# RF_Transceiver_LM6002D_Power.net
KiCad netlist of a schematic drawn in Altium Designer
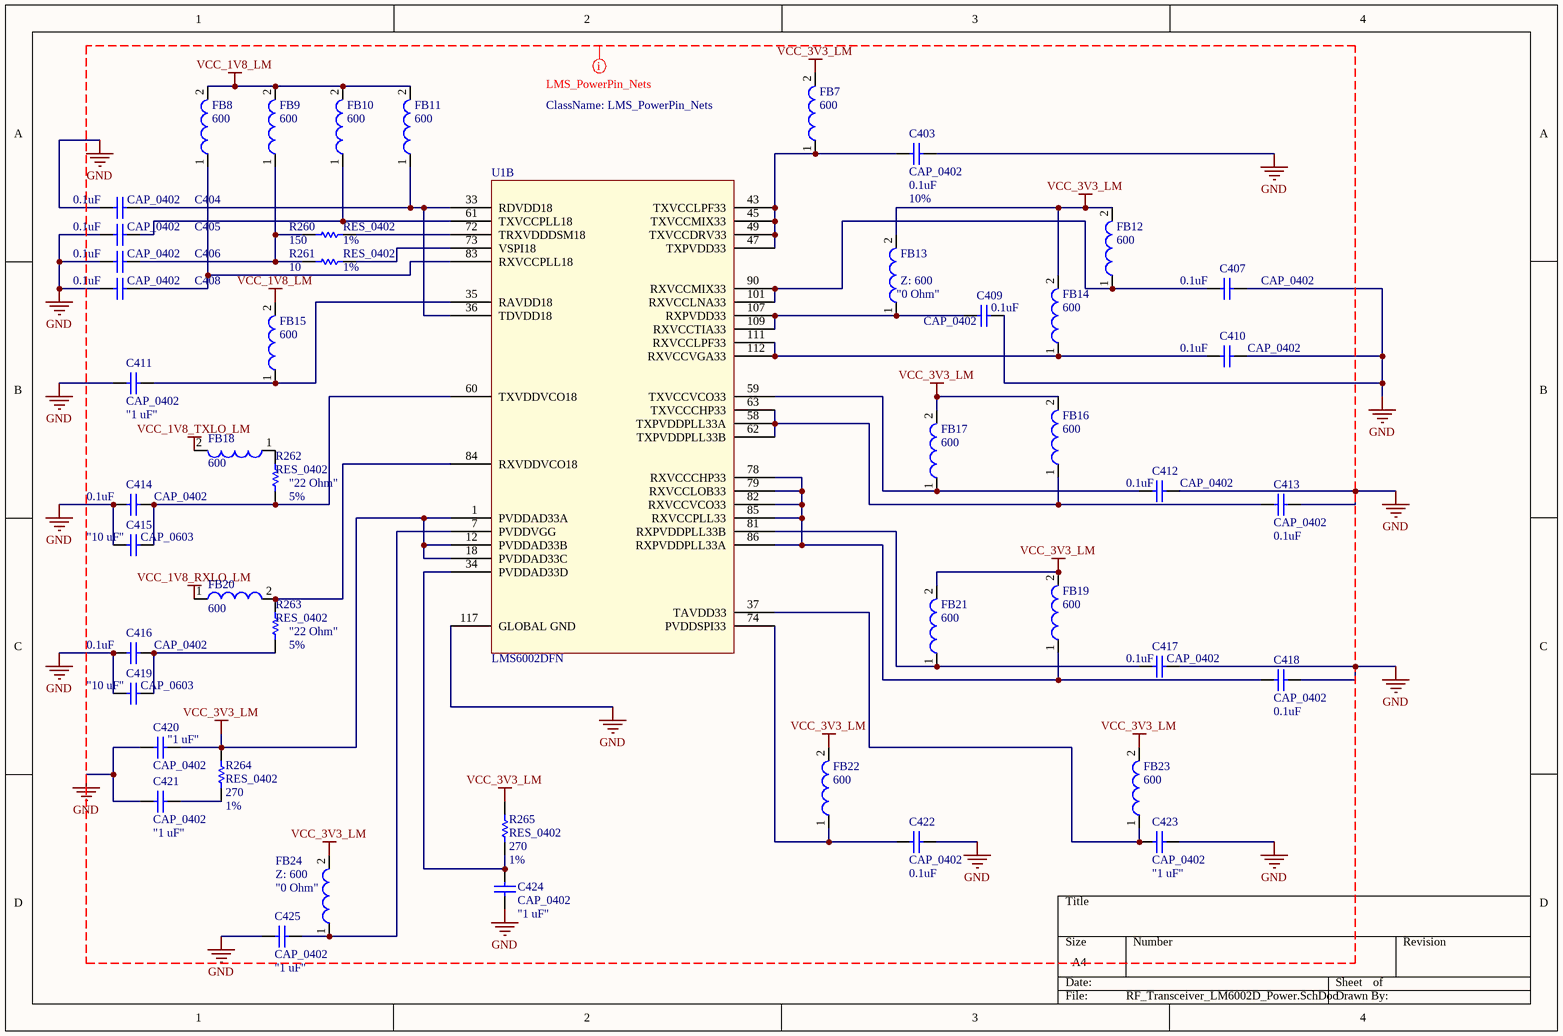
[diagram p0: RF_Transceiver_LM6002D_Power.SchDoc]

(export (version "E")
  (design (tool "Eeschema 10.0.6"))
  (components
    (comp (ref "C403")
      (value "CAP_0402")
      (footprint "CAPC0402(1005)60_N")
      (description "0.1uf, ceramic, 10%, 6.3V, X5R, 0402")
      (fields
        (field (name "ALTIUM_VALUE") "0.1uF")
        (field (name "TOLERANCE") "10%")
        (field (name "PART NUMBER") "C1005X5R0J104K")
        (field (name "MANUFACTURER") "TDK Corporation")
      )
      (libsource (lib "COMRAD_Database") (part "CAP_0402"))
    )
    (comp (ref "C404")
      (value "CAP_0402")
      (footprint "CAPC0402(1005)60_N")
      (description "0.1uf, ceramic, 10%, 6.3V, X5R, 0402")
      (fields
        (field (name "ALTIUM_VALUE") "0.1uF")
        (field (name "TOLERANCE") "10%")
        (field (name "PART NUMBER") "C1005X5R0J104K")
      )
      (libsource (lib "COMRAD_Database") (part "CAP_0402"))
    )
    (comp (ref "C405")
      (value "CAP_0402")
      (footprint "CAPC0402(1005)60_N")
      (description "0.1uf, ceramic, 10%, 6.3V, X5R, 0402")
      (fields
        (field (name "ALTIUM_VALUE") "0.1uF")
        (field (name "TOLERANCE") "10%")
        (field (name "PART NUMBER") "C1005X5R0J104K")
      )
      (libsource (lib "COMRAD_Database") (part "CAP_0402"))
    )
    (comp (ref "C406")
      (value "CAP_0402")
      (footprint "CAPC0402(1005)60_N")
      (description "0.1uf, ceramic, 10%, 6.3V, X5R, 0402")
      (fields
        (field (name "ALTIUM_VALUE") "0.1uF")
        (field (name "TOLERANCE") "10%")
        (field (name "PART NUMBER") "C1005X5R0J104K")
      )
      (libsource (lib "COMRAD_Database") (part "CAP_0402"))
    )
    (comp (ref "C407")
      (value "CAP_0402")
      (footprint "CAPC0402(1005)60_N")
      (description "0.1uf, ceramic, 10%, 6.3V, X5R, 0402")
      (fields
        (field (name "ALTIUM_VALUE") "0.1uF")
        (field (name "TOLERANCE") "10%")
        (field (name "PART NUMBER") "C1005X5R0J104K")
      )
      (libsource (lib "COMRAD_Database") (part "CAP_0402"))
    )
    (comp (ref "C408")
      (value "CAP_0402")
      (footprint "CAPC0402(1005)60_N")
      (description "0.1uf, ceramic, 10%, 6.3V, X5R, 0402")
      (fields
        (field (name "ALTIUM_VALUE") "0.1uF")
        (field (name "TOLERANCE") "10%")
        (field (name "PART NUMBER") "C1005X5R0J104K")
      )
      (libsource (lib "COMRAD_Database") (part "CAP_0402"))
    )
    (comp (ref "C409")
      (value "CAP_0402")
      (footprint "CAPC0402(1005)60_N")
      (description "0.1uf, ceramic, 10%, 6.3V, X5R, 0402")
      (fields
        (field (name "ALTIUM_VALUE") "0.1uF")
        (field (name "TOLERANCE") "10%")
        (field (name "PART NUMBER") "C1005X5R0J104K")
      )
      (libsource (lib "COMRAD_Database") (part "CAP_0402"))
    )
    (comp (ref "C410")
      (value "CAP_0402")
      (footprint "CAPC0402(1005)60_N")
      (description "0.1uf, ceramic, 10%, 6.3V, X5R, 0402")
      (fields
        (field (name "ALTIUM_VALUE") "0.1uF")
        (field (name "TOLERANCE") "10%")
        (field (name "PART NUMBER") "C1005X5R0J104K")
      )
      (libsource (lib "COMRAD_Database") (part "CAP_0402"))
    )
    (comp (ref "C411")
      (value "CAP_0402")
      (footprint "CAPC0402(1005)60_N")
      (description "C 1 uF 10V 0402 X5R")
      (fields
        (field (name "ALTIUM_VALUE") "\"1 uF\"")
        (field (name "PART NUMBER") "\"MCCA000506\"")
        (field (name "MANUFACTURER") "MULTICOMP")
      )
      (libsource (lib "COMRAD_Database") (part "CAP_0402"))
    )
    (comp (ref "C412")
      (value "CAP_0402")
      (footprint "CAPC0402(1005)60_N")
      (description "0.1uf, ceramic, 10%, 6.3V, X5R, 0402")
      (fields
        (field (name "ALTIUM_VALUE") "0.1uF")
        (field (name "TOLERANCE") "10%")
        (field (name "PART NUMBER") "C1005X5R0J104K")
      )
      (libsource (lib "COMRAD_Database") (part "CAP_0402"))
    )
    (comp (ref "C413")
      (value "CAP_0402")
      (footprint "CAPC0402(1005)60_N")
      (description "0.1uf, ceramic, 10%, 6.3V, X5R, 0402")
      (fields
        (field (name "ALTIUM_VALUE") "0.1uF")
        (field (name "TOLERANCE") "10%")
        (field (name "PART NUMBER") "C1005X5R0J104K")
      )
      (libsource (lib "COMRAD_Database") (part "CAP_0402"))
    )
    (comp (ref "C414")
      (value "CAP_0402")
      (footprint "CAPC0402(1005)60_N")
      (description "0.1uf, ceramic, 10%, 6.3V, X5R, 0402")
      (fields
        (field (name "ALTIUM_VALUE") "0.1uF")
        (field (name "TOLERANCE") "10%")
        (field (name "PART NUMBER") "C1005X5R0J104K")
      )
      (libsource (lib "COMRAD_Database") (part "CAP_0402"))
    )
    (comp (ref "C415")
      (value "CAP_0603")
      (footprint "CAPC0603(1608)100_N:CAPC0603(1608)100_N")
      (description "C 10 uF 6.3 V 0603 X5R")
      (fields
        (field (name "ALTIUM_VALUE") "\"10 uF\"")
        (field (name "PART NUMBER") "\"MCCA000517\"")
        (field (name "MANUFACTURER") "Multicomp")
      )
      (libsource (lib "COMRAD_Database") (part "CAP_0603"))
    )
    (comp (ref "C416")
      (value "CAP_0402")
      (footprint "CAPC0402(1005)60_N")
      (description "0.1uf, ceramic, 10%, 6.3V, X5R, 0402")
      (fields
        (field (name "ALTIUM_VALUE") "0.1uF")
        (field (name "TOLERANCE") "10%")
        (field (name "PART NUMBER") "C1005X5R0J104K")
      )
      (libsource (lib "COMRAD_Database") (part "CAP_0402"))
    )
    (comp (ref "C417")
      (value "CAP_0402")
      (footprint "CAPC0402(1005)60_N")
      (description "0.1uf, ceramic, 10%, 6.3V, X5R, 0402")
      (fields
        (field (name "ALTIUM_VALUE") "0.1uF")
        (field (name "TOLERANCE") "10%")
        (field (name "PART NUMBER") "C1005X5R0J104K")
      )
      (libsource (lib "COMRAD_Database") (part "CAP_0402"))
    )
    (comp (ref "C418")
      (value "CAP_0402")
      (footprint "CAPC0402(1005)60_N")
      (description "0.1uf, ceramic, 10%, 6.3V, X5R, 0402")
      (fields
        (field (name "ALTIUM_VALUE") "0.1uF")
        (field (name "TOLERANCE") "10%")
        (field (name "PART NUMBER") "C1005X5R0J104K")
      )
      (libsource (lib "COMRAD_Database") (part "CAP_0402"))
    )
    (comp (ref "C419")
      (value "CAP_0603")
      (footprint "CAPC0603(1608)100_N:CAPC0603(1608)100_N")
      (description "C 10 uF 6.3 V 0603 X5R")
      (fields
        (field (name "ALTIUM_VALUE") "\"10 uF\"")
        (field (name "PART NUMBER") "\"MCCA000517\"")
        (field (name "MANUFACTURER") "Multicomp")
      )
      (libsource (lib "COMRAD_Database") (part "CAP_0603"))
    )
    (comp (ref "C420")
      (value "CAP_0402")
      (footprint "CAPC0402(1005)60_N")
      (description "C 1 uF 10V 0402 X5R")
      (fields
        (field (name "ALTIUM_VALUE") "\"1 uF\"")
        (field (name "PART NUMBER") "\"MCCA000506\"")
        (field (name "MANUFACTURER") "MULTICOMP")
      )
      (libsource (lib "COMRAD_Database") (part "CAP_0402"))
    )
    (comp (ref "C421")
      (value "CAP_0402")
      (footprint "CAPC0402(1005)60_N")
      (description "C 1 uF 10V 0402 X5R")
      (fields
        (field (name "ALTIUM_VALUE") "\"1 uF\"")
        (field (name "PART NUMBER") "\"MCCA000506\"")
        (field (name "MANUFACTURER") "MULTICOMP")
      )
      (libsource (lib "COMRAD_Database") (part "CAP_0402"))
    )
    (comp (ref "C422")
      (value "CAP_0402")
      (footprint "CAPC0402(1005)60_N")
      (description "0.1uf, ceramic, 10%, 6.3V, X5R, 0402")
      (fields
        (field (name "ALTIUM_VALUE") "0.1uF")
        (field (name "TOLERANCE") "10%")
        (field (name "PART NUMBER") "C1005X5R0J104K")
      )
      (libsource (lib "COMRAD_Database") (part "CAP_0402"))
    )
    (comp (ref "C423")
      (value "CAP_0402")
      (footprint "CAPC0402(1005)60_N")
      (description "C 1 uF 10V 0402 X5R")
      (fields
        (field (name "ALTIUM_VALUE") "\"1 uF\"")
        (field (name "PART NUMBER") "\"MCCA000506\"")
        (field (name "MANUFACTURER") "MULTICOMP")
      )
      (libsource (lib "COMRAD_Database") (part "CAP_0402"))
    )
    (comp (ref "C424")
      (value "CAP_0402")
      (footprint "CAPC0402(1005)60_N")
      (description "C 1 uF 10V 0402 X5R")
      (fields
        (field (name "ALTIUM_VALUE") "\"1 uF\"")
        (field (name "PART NUMBER") "\"MCCA000506\"")
        (field (name "MANUFACTURER") "MULTICOMP")
      )
      (libsource (lib "COMRAD_Database") (part "CAP_0402"))
    )
    (comp (ref "C425")
      (value "CAP_0402")
      (footprint "CAPC0402(1005)60_N")
      (description "C 1 uF 10V 0402 X5R")
      (fields
        (field (name "ALTIUM_VALUE") "\"1 uF\"")
        (field (name "PART NUMBER") "\"MCCA000506\"")
        (field (name "MANUFACTURER") "MULTICOMP")
      )
      (libsource (lib "COMRAD_Database") (part "CAP_0402"))
    )
    (comp (ref "FB7")
      (value "FerriteBead")
      (footprint "Inductor0402(1005)")
      (description "Ferrite 300mA 600ohm 0402")
      (fields
        (field (name "Z") "600")
        (field (name "PART NUMBER") "\"MMZ1005S601C\"")
        (field (name "MANUFACTURER") "TDK")
      )
      (libsource (lib "COMRAD_Database") (part "FerriteBead"))
    )
    (comp (ref "FB8")
      (value "FerriteBead")
      (footprint "Inductor0402(1005)")
      (description "Ferrite 300mA 600ohm 0402")
      (fields
        (field (name "Z") "600")
        (field (name "PART NUMBER") "\"MMZ1005S601C\"")
        (field (name "MANUFACTURER") "TDK")
      )
      (libsource (lib "COMRAD_Database") (part "FerriteBead"))
    )
    (comp (ref "FB9")
      (value "FerriteBead")
      (footprint "Inductor0402(1005)")
      (description "Ferrite 300mA 600ohm 0402")
      (fields
        (field (name "Z") "600")
        (field (name "PART NUMBER") "\"MMZ1005S601C\"")
        (field (name "MANUFACTURER") "TDK")
      )
      (libsource (lib "COMRAD_Database") (part "FerriteBead"))
    )
    (comp (ref "FB10")
      (value "FerriteBead")
      (footprint "Inductor0402(1005)")
      (description "Ferrite 300mA 600ohm 0402")
      (fields
        (field (name "Z") "600")
        (field (name "PART NUMBER") "\"MMZ1005S601C\"")
        (field (name "MANUFACTURER") "TDK")
      )
      (libsource (lib "COMRAD_Database") (part "FerriteBead"))
    )
    (comp (ref "FB11")
      (value "FerriteBead")
      (footprint "Inductor0402(1005)")
      (description "Ferrite 300mA 600ohm 0402")
      (fields
        (field (name "Z") "600")
        (field (name "PART NUMBER") "\"MMZ1005S601C\"")
        (field (name "MANUFACTURER") "TDK")
      )
      (libsource (lib "COMRAD_Database") (part "FerriteBead"))
    )
    (comp (ref "FB12")
      (value "FerriteBead")
      (footprint "Inductor0402(1005)")
      (description "Ferrite 300mA 600ohm 0402")
      (fields
        (field (name "Z") "600")
        (field (name "PART NUMBER") "\"MMZ1005S601C\"")
        (field (name "MANUFACTURER") "TDK")
      )
      (libsource (lib "COMRAD_Database") (part "FerriteBead"))
    )
    (comp (ref "FB13")
      (value "\"0 Ohm\"")
      (footprint "Inductor0402(1005)")
      (description "Ferrite 300mA 600ohm 0402")
      (fields
        (field (name "Z") "600")
        (field (name "PART NUMBER") "\"MMZ1005S601C\"")
        (field (name "MANUFACTURER") "TDK")
      )
      (libsource (lib "COMRAD_Database") (part "FerriteBead"))
    )
    (comp (ref "FB14")
      (value "FerriteBead")
      (footprint "Inductor0402(1005)")
      (description "Ferrite 300mA 600ohm 0402")
      (fields
        (field (name "Z") "600")
        (field (name "PART NUMBER") "\"MMZ1005S601C\"")
        (field (name "MANUFACTURER") "TDK")
      )
      (libsource (lib "COMRAD_Database") (part "FerriteBead"))
    )
    (comp (ref "FB15")
      (value "FerriteBead")
      (footprint "Inductor0402(1005)")
      (description "Ferrite 300mA 600ohm 0402")
      (fields
        (field (name "Z") "600")
        (field (name "PART NUMBER") "\"MMZ1005S601C\"")
        (field (name "MANUFACTURER") "TDK")
      )
      (libsource (lib "COMRAD_Database") (part "FerriteBead"))
    )
    (comp (ref "FB16")
      (value "FerriteBead")
      (footprint "Inductor0402(1005)")
      (description "Ferrite 300mA 600ohm 0402")
      (fields
        (field (name "Z") "600")
        (field (name "PART NUMBER") "\"MMZ1005S601C\"")
        (field (name "MANUFACTURER") "TDK")
      )
      (libsource (lib "COMRAD_Database") (part "FerriteBead"))
    )
    (comp (ref "FB17")
      (value "FerriteBead")
      (footprint "Inductor0402(1005)")
      (description "Ferrite 300mA 600ohm 0402")
      (fields
        (field (name "Z") "600")
        (field (name "PART NUMBER") "\"MMZ1005S601C\"")
        (field (name "MANUFACTURER") "TDK")
      )
      (libsource (lib "COMRAD_Database") (part "FerriteBead"))
    )
    (comp (ref "FB18")
      (value "FerriteBead")
      (footprint "Inductor0402(1005)")
      (description "Ferrite 300mA 600ohm 0402")
      (fields
        (field (name "Z") "600")
        (field (name "PART NUMBER") "\"MMZ1005S601C\"")
        (field (name "MANUFACTURER") "TDK")
      )
      (libsource (lib "COMRAD_Database") (part "FerriteBead"))
    )
    (comp (ref "FB19")
      (value "FerriteBead")
      (footprint "Inductor0402(1005)")
      (description "Ferrite 300mA 600ohm 0402")
      (fields
        (field (name "Z") "600")
        (field (name "PART NUMBER") "\"MMZ1005S601C\"")
        (field (name "MANUFACTURER") "TDK")
      )
      (libsource (lib "COMRAD_Database") (part "FerriteBead"))
    )
    (comp (ref "FB20")
      (value "FerriteBead")
      (footprint "Inductor0402(1005)")
      (description "Ferrite 300mA 600ohm 0402")
      (fields
        (field (name "Z") "600")
        (field (name "PART NUMBER") "\"MMZ1005S601C\"")
        (field (name "MANUFACTURER") "TDK")
      )
      (libsource (lib "COMRAD_Database") (part "FerriteBead"))
    )
    (comp (ref "FB21")
      (value "FerriteBead")
      (footprint "Inductor0402(1005)")
      (description "Ferrite 300mA 600ohm 0402")
      (fields
        (field (name "Z") "600")
        (field (name "PART NUMBER") "\"MMZ1005S601C\"")
        (field (name "MANUFACTURER") "TDK")
      )
      (libsource (lib "COMRAD_Database") (part "FerriteBead"))
    )
    (comp (ref "FB22")
      (value "FerriteBead")
      (footprint "Inductor0402(1005)")
      (description "Ferrite 300mA 600ohm 0402")
      (fields
        (field (name "Z") "600")
        (field (name "PART NUMBER") "\"MMZ1005S601C\"")
        (field (name "MANUFACTURER") "TDK")
      )
      (libsource (lib "COMRAD_Database") (part "FerriteBead"))
    )
    (comp (ref "FB23")
      (value "FerriteBead")
      (footprint "Inductor0402(1005)")
      (description "Ferrite 300mA 600ohm 0402")
      (fields
        (field (name "Z") "600")
        (field (name "PART NUMBER") "\"MMZ1005S601C\"")
        (field (name "MANUFACTURER") "TDK")
      )
      (libsource (lib "COMRAD_Database") (part "FerriteBead"))
    )
    (comp (ref "FB24")
      (value "\"0 Ohm\"")
      (footprint "Inductor0402(1005)")
      (description "Ferrite 300mA 600ohm 0402")
      (fields
        (field (name "Z") "600")
        (field (name "PART NUMBER") "\"MMZ1005S601C\"")
        (field (name "MANUFACTURER") "TDK")
      )
      (libsource (lib "COMRAD_Database") (part "FerriteBead"))
    )
    (comp (ref "R260")
      (value "RES_0402")
      (footprint "RESC0402(1005)_N")
      (description "RES 150 OHM 1/10W 1% 0402 SMD")
      (fields
        (field (name "ALTIUM_VALUE") "150")
        (field (name "TOLERANCE") "1%")
        (field (name "PART NUMBER") "ERJ-2RKF1500X")
        (field (name "MANUFACTURER") "Panasonic Electronic Components")
      )
      (libsource (lib "COMRAD_Database") (part "RES_0402"))
    )
    (comp (ref "R261")
      (value "RES_0402")
      (footprint "RESC0402(1005)_N")
      (description "RES 10.0 OHM 1/10W 1% 0402 SMD")
      (fields
        (field (name "ALTIUM_VALUE") "10")
        (field (name "TOLERANCE") "1%")
        (field (name "PART NUMBER") "ERJ-2RKF10R0X")
        (field (name "MANUFACTURER") "Panasonic Electronic Components")
      )
      (libsource (lib "COMRAD_Database") (part "RES_0402"))
    )
    (comp (ref "R262")
      (value "RES_0402")
      (footprint "RESC0402(1005)_N")
      (description "R 22 Ohm 5% 63mW 0402")
      (fields
        (field (name "ALTIUM_VALUE") "\"22 Ohm\"")
        (field (name "TOLERANCE") "5%")
        (field (name "PART NUMBER") "\"RC0402JR-0722RL\"")
        (field (name "MANUFACTURER") "YAGEO")
      )
      (libsource (lib "COMRAD_Database") (part "RES_0402"))
    )
    (comp (ref "R263")
      (value "RES_0402")
      (footprint "RESC0402(1005)_N")
      (description "R 22 Ohm 5% 63mW 0402")
      (fields
        (field (name "ALTIUM_VALUE") "\"22 Ohm\"")
        (field (name "TOLERANCE") "5%")
        (field (name "PART NUMBER") "\"RC0402JR-0722RL\"")
        (field (name "MANUFACTURER") "YAGEO")
      )
      (libsource (lib "COMRAD_Database") (part "RES_0402"))
    )
    (comp (ref "R264")
      (value "RES_0402")
      (footprint "RESC0402(1005)_N")
      (description "RES 270 OHM 1/10W 1% 0402 SMD")
      (fields
        (field (name "ALTIUM_VALUE") "270")
        (field (name "TOLERANCE") "1%")
        (field (name "PART NUMBER") "ERJ-2RKF2700X")
        (field (name "MANUFACTURER") "Panasonic Electronic Components")
      )
      (libsource (lib "COMRAD_Database") (part "RES_0402"))
    )
    (comp (ref "R265")
      (value "RES_0402")
      (footprint "RESC0402(1005)_N")
      (description "RES 270 OHM 1/10W 1% 0402 SMD")
      (fields
        (field (name "ALTIUM_VALUE") "270")
        (field (name "TOLERANCE") "1%")
        (field (name "PART NUMBER") "ERJ-2RKF2700X")
        (field (name "MANUFACTURER") "Panasonic Electronic Components")
      )
      (libsource (lib "COMRAD_Database") (part "RES_0402"))
    )
    (comp (ref "U1")
      (value "LMS6002DFN")
      (footprint "RF_Transceiver_LimeMicro_LMS6002D_DQFN-116")
      (description "RF Transceiver LMS6002D, 120 pin DQFN package, 1.8V and 3.3V")
      (fields (field (name "MANUFACTURER") "Lime Micro"))
      (libsource (lib "COMRAD_Database") (part "RF_Transceiver_LimeMicro_LMS6002D"))
    )
  )
  (nets
    (net (code "1") (name "GND") (class "Default")
      (node (ref "C403") (pin "1") (pinfunction "1_1") (pintype "passive"))
      (node (ref "C404") (pin "2") (pinfunction "2_2") (pintype "passive"))
      (node (ref "C405") (pin "2") (pinfunction "2_2") (pintype "passive"))
      (node (ref "C406") (pin "2") (pinfunction "2_2") (pintype "passive"))
      (node (ref "C407") (pin "1") (pinfunction "1_1") (pintype "passive"))
      (node (ref "C408") (pin "2") (pinfunction "2_2") (pintype "passive"))
      (node (ref "C409") (pin "1") (pinfunction "1_1") (pintype "passive"))
      (node (ref "C410") (pin "1") (pinfunction "1_1") (pintype "passive"))
      (node (ref "C411") (pin "1") (pinfunction "1_1") (pintype "passive"))
      (node (ref "C412") (pin "1") (pinfunction "1_1") (pintype "passive"))
      (node (ref "C413") (pin "1") (pinfunction "1_1") (pintype "passive"))
      (node (ref "C414") (pin "2") (pinfunction "2_2") (pintype "passive"))
      (node (ref "C415") (pin "1") (pinfunction "1_1") (pintype "passive"))
      (node (ref "C416") (pin "2") (pinfunction "2_2") (pintype "passive"))
      (node (ref "C417") (pin "1") (pinfunction "1_1") (pintype "passive"))
      (node (ref "C418") (pin "1") (pinfunction "1_1") (pintype "passive"))
      (node (ref "C419") (pin "1") (pinfunction "1_1") (pintype "passive"))
      (node (ref "C420") (pin "1") (pinfunction "1_1") (pintype "passive"))
      (node (ref "C421") (pin "1") (pinfunction "1_1") (pintype "passive"))
      (node (ref "C422") (pin "1") (pinfunction "1_1") (pintype "passive"))
      (node (ref "C423") (pin "2") (pinfunction "2_2") (pintype "passive"))
      (node (ref "C424") (pin "1") (pinfunction "1_1") (pintype "passive"))
      (node (ref "C425") (pin "1") (pinfunction "1_1") (pintype "passive"))
      (node (ref "U1") (pin "117") (pinfunction "GLOBAL_GND_117") (pintype "power_in"))
    )
    (net (code "2") (name "Net-(C406-Pad1)") (class "Default")
      (node (ref "C406") (pin "1") (pinfunction "1_1") (pintype "passive"))
      (node (ref "FB9") (pin "1") (pinfunction "1_1") (pintype "passive"))
      (node (ref "R260") (pin "1") (pinfunction "1_1") (pintype "passive"))
      (node (ref "R261") (pin "1") (pinfunction "1_1") (pintype "passive"))
    )
    (net (code "3") (name "Net-(C416-Pad1)") (class "Default")
      (node (ref "C416") (pin "1") (pinfunction "1_1") (pintype "passive"))
      (node (ref "C419") (pin "2") (pinfunction "2_2") (pintype "passive"))
      (node (ref "R263") (pin "1") (pinfunction "1_1") (pintype "passive"))
    )
    (net (code "4") (name "Net-(C421-Pad2)") (class "Default")
      (node (ref "C421") (pin "2") (pinfunction "2_2") (pintype "passive"))
      (node (ref "R264") (pin "1") (pinfunction "1_1") (pintype "passive"))
    )
    (net (code "5") (name "Net-(FB18-Pad1)") (class "Default")
      (node (ref "FB18") (pin "1") (pinfunction "1_1") (pintype "passive"))
      (node (ref "R262") (pin "2") (pinfunction "2_2") (pintype "passive"))
    )
    (net (code "6") (name "Net-(U1B-PVDDAD33D)") (class "Default")
      (node (ref "C424") (pin "2") (pinfunction "2_2") (pintype "passive"))
      (node (ref "R265") (pin "2") (pinfunction "2_2") (pintype "passive"))
      (node (ref "U1") (pin "34") (pinfunction "PVDDAD33D_34") (pintype "power_in"))
    )
    (net (code "7") (name "Net-(U1B-PVDDSPI33)") (class "Default")
      (node (ref "C422") (pin "2") (pinfunction "2_2") (pintype "passive"))
      (node (ref "FB22") (pin "1") (pinfunction "1_1") (pintype "passive"))
      (node (ref "U1") (pin "74") (pinfunction "PVDDSPI33_74") (pintype "power_in"))
    )
    (net (code "8") (name "Net-(U1B-PVDDVGG)") (class "Default")
      (node (ref "C425") (pin "2") (pinfunction "2_2") (pintype "passive"))
      (node (ref "FB24") (pin "1") (pinfunction "1_1") (pintype "passive"))
      (node (ref "U1") (pin "7") (pinfunction "PVDDVGG_7") (pintype "power_in"))
    )
    (net (code "9") (name "Net-(U1B-RAVDD18)") (class "Default")
      (node (ref "C411") (pin "2") (pinfunction "2_2") (pintype "passive"))
      (node (ref "FB15") (pin "1") (pinfunction "1_1") (pintype "passive"))
      (node (ref "U1") (pin "35") (pinfunction "RAVDD18_35") (pintype "power_in"))
    )
    (net (code "10") (name "Net-(U1B-RDVDD18)") (class "Default")
      (node (ref "C404") (pin "1") (pinfunction "1_1") (pintype "passive"))
      (node (ref "FB11") (pin "1") (pinfunction "1_1") (pintype "passive"))
      (node (ref "U1") (pin "33") (pinfunction "RDVDD18_33") (pintype "power_in"))
      (node (ref "U1") (pin "36") (pinfunction "TDVDD18_36") (pintype "power_in"))
    )
    (net (code "11") (name "Net-(U1B-RXPVDD33)") (class "Default")
      (node (ref "C409") (pin "2") (pinfunction "2_2") (pintype "passive"))
      (node (ref "FB13") (pin "1") (pinfunction "1_1") (pintype "passive"))
      (node (ref "U1") (pin "107") (pinfunction "RXPVDD33_107") (pintype "power_in"))
      (node (ref "U1") (pin "109") (pinfunction "RXVCCTIA33_109") (pintype "power_in"))
    )
    (net (code "12") (name "Net-(U1B-RXPVDDPLL33A)") (class "Default")
      (node (ref "C418") (pin "2") (pinfunction "2_2") (pintype "passive"))
      (node (ref "FB19") (pin "1") (pinfunction "1_1") (pintype "passive"))
      (node (ref "U1") (pin "78") (pinfunction "RXVCCCHP33_78") (pintype "power_in"))
      (node (ref "U1") (pin "79") (pinfunction "RXVCCLOB33_79") (pintype "power_in"))
      (node (ref "U1") (pin "82") (pinfunction "RXVCCVCO33_82") (pintype "power_in"))
      (node (ref "U1") (pin "85") (pinfunction "RXVCCPLL33_85") (pintype "power_in"))
      (node (ref "U1") (pin "86") (pinfunction "RXPVDDPLL33A_86") (pintype "power_in"))
    )
    (net (code "13") (name "Net-(U1B-RXPVDDPLL33B)") (class "Default")
      (node (ref "C417") (pin "2") (pinfunction "2_2") (pintype "passive"))
      (node (ref "FB21") (pin "1") (pinfunction "1_1") (pintype "passive"))
      (node (ref "U1") (pin "81") (pinfunction "RXPVDDPLL33B_81") (pintype "power_in"))
    )
    (net (code "14") (name "Net-(U1B-RXVCCLNA33)") (class "Default")
      (node (ref "C407") (pin "2") (pinfunction "2_2") (pintype "passive"))
      (node (ref "FB12") (pin "1") (pinfunction "1_1") (pintype "passive"))
      (node (ref "U1") (pin "101") (pinfunction "RXVCCLNA33_101") (pintype "power_in"))
      (node (ref "U1") (pin "90") (pinfunction "RXVCCMIX33_90") (pintype "power_in"))
    )
    (net (code "15") (name "Net-(U1B-RXVCCLPF33)") (class "Default")
      (node (ref "C410") (pin "2") (pinfunction "2_2") (pintype "passive"))
      (node (ref "FB14") (pin "1") (pinfunction "1_1") (pintype "passive"))
      (node (ref "U1") (pin "111") (pinfunction "RXVCCLPF33_111") (pintype "power_in"))
      (node (ref "U1") (pin "112") (pinfunction "RXVCCVGA33_112") (pintype "power_in"))
    )
    (net (code "16") (name "Net-(U1B-RXVCCPLL18)") (class "Default")
      (node (ref "C408") (pin "1") (pinfunction "1_1") (pintype "passive"))
      (node (ref "FB8") (pin "1") (pinfunction "1_1") (pintype "passive"))
      (node (ref "U1") (pin "83") (pinfunction "RXVCCPLL18_83") (pintype "power_in"))
    )
    (net (code "17") (name "Net-(U1B-RXVDDVCO18)") (class "Default")
      (node (ref "FB20") (pin "2") (pinfunction "2_2") (pintype "passive"))
      (node (ref "R263") (pin "2") (pinfunction "2_2") (pintype "passive"))
      (node (ref "U1") (pin "84") (pinfunction "RXVDDVCO18_84") (pintype "power_in"))
    )
    (net (code "18") (name "Net-(U1B-TAVDD33)") (class "Default")
      (node (ref "C423") (pin "1") (pinfunction "1_1") (pintype "passive"))
      (node (ref "FB23") (pin "1") (pinfunction "1_1") (pintype "passive"))
      (node (ref "U1") (pin "37") (pinfunction "TAVDD33_37") (pintype "power_in"))
    )
    (net (code "19") (name "Net-(U1B-TRXVDDDSM18)") (class "Default")
      (node (ref "R260") (pin "2") (pinfunction "2_2") (pintype "passive"))
      (node (ref "U1") (pin "72") (pinfunction "TRXVDDDSM18_72") (pintype "power_in"))
    )
    (net (code "20") (name "Net-(U1B-TXPVDD33)") (class "Default")
      (node (ref "C403") (pin "2") (pinfunction "2_2") (pintype "passive"))
      (node (ref "FB7") (pin "1") (pinfunction "1_1") (pintype "passive"))
      (node (ref "U1") (pin "43") (pinfunction "TXVCCLPF33_43") (pintype "power_in"))
      (node (ref "U1") (pin "45") (pinfunction "TXVCCMIX33_45") (pintype "power_in"))
      (node (ref "U1") (pin "47") (pinfunction "TXPVDD33_47") (pintype "power_in"))
      (node (ref "U1") (pin "49") (pinfunction "TXVCCDRV33_49") (pintype "power_in"))
    )
    (net (code "21") (name "Net-(U1B-TXPVDDPLL33A)") (class "Default")
      (node (ref "C413") (pin "2") (pinfunction "2_2") (pintype "passive"))
      (node (ref "FB16") (pin "1") (pinfunction "1_1") (pintype "passive"))
      (node (ref "U1") (pin "58") (pinfunction "TXPVDDPLL33A_58") (pintype "power_in"))
      (node (ref "U1") (pin "62") (pinfunction "TXPVDDPLL33B_62") (pintype "power_in"))
      (node (ref "U1") (pin "63") (pinfunction "TXVCCCHP33_63") (pintype "power_in"))
    )
    (net (code "22") (name "Net-(U1B-TXVCCPLL18)") (class "Default")
      (node (ref "C405") (pin "1") (pinfunction "1_1") (pintype "passive"))
      (node (ref "FB10") (pin "1") (pinfunction "1_1") (pintype "passive"))
      (node (ref "U1") (pin "61") (pinfunction "TXVCCPLL18_61") (pintype "power_in"))
    )
    (net (code "23") (name "Net-(U1B-TXVCCVCO33)") (class "Default")
      (node (ref "C412") (pin "2") (pinfunction "2_2") (pintype "passive"))
      (node (ref "FB17") (pin "1") (pinfunction "1_1") (pintype "passive"))
      (node (ref "U1") (pin "59") (pinfunction "TXVCCVCO33_59") (pintype "power_in"))
    )
    (net (code "24") (name "Net-(U1B-TXVDDVCO18)") (class "Default")
      (node (ref "C414") (pin "1") (pinfunction "1_1") (pintype "passive"))
      (node (ref "C415") (pin "2") (pinfunction "2_2") (pintype "passive"))
      (node (ref "R262") (pin "1") (pinfunction "1_1") (pintype "passive"))
      (node (ref "U1") (pin "60") (pinfunction "TXVDDVCO18_60") (pintype "power_in"))
    )
    (net (code "25") (name "Net-(U1B-VSPI18)") (class "Default")
      (node (ref "R261") (pin "2") (pinfunction "2_2") (pintype "passive"))
      (node (ref "U1") (pin "73") (pinfunction "VSPI18_73") (pintype "power_in"))
    )
    (net (code "26") (name "VCC_1V8_LM") (class "Default")
      (node (ref "FB10") (pin "2") (pinfunction "2_2") (pintype "passive"))
      (node (ref "FB11") (pin "2") (pinfunction "2_2") (pintype "passive"))
      (node (ref "FB15") (pin "2") (pinfunction "2_2") (pintype "passive"))
      (node (ref "FB8") (pin "2") (pinfunction "2_2") (pintype "passive"))
      (node (ref "FB9") (pin "2") (pinfunction "2_2") (pintype "passive"))
    )
    (net (code "27") (name "VCC_1V8_RXLO_LM") (class "Default")
      (node (ref "FB20") (pin "1") (pinfunction "1_1") (pintype "passive"))
    )
    (net (code "28") (name "VCC_1V8_TXLO_LM") (class "Default")
      (node (ref "FB18") (pin "2") (pinfunction "2_2") (pintype "passive"))
    )
    (net (code "29") (name "VCC_3V3_LM") (class "Default")
      (node (ref "C420") (pin "2") (pinfunction "2_2") (pintype "passive"))
      (node (ref "FB12") (pin "2") (pinfunction "2_2") (pintype "passive"))
      (node (ref "FB13") (pin "2") (pinfunction "2_2") (pintype "passive"))
      (node (ref "FB14") (pin "2") (pinfunction "2_2") (pintype "passive"))
      (node (ref "FB16") (pin "2") (pinfunction "2_2") (pintype "passive"))
      (node (ref "FB17") (pin "2") (pinfunction "2_2") (pintype "passive"))
      (node (ref "FB19") (pin "2") (pinfunction "2_2") (pintype "passive"))
      (node (ref "FB21") (pin "2") (pinfunction "2_2") (pintype "passive"))
      (node (ref "FB22") (pin "2") (pinfunction "2_2") (pintype "passive"))
      (node (ref "FB23") (pin "2") (pinfunction "2_2") (pintype "passive"))
      (node (ref "FB24") (pin "2") (pinfunction "2_2") (pintype "passive"))
      (node (ref "FB7") (pin "2") (pinfunction "2_2") (pintype "passive"))
      (node (ref "R264") (pin "2") (pinfunction "2_2") (pintype "passive"))
      (node (ref "R265") (pin "1") (pinfunction "1_1") (pintype "passive"))
      (node (ref "U1") (pin "1") (pinfunction "PVDDAD33A_1") (pintype "power_in"))
      (node (ref "U1") (pin "12") (pinfunction "PVDDAD33B_12") (pintype "power_in"))
      (node (ref "U1") (pin "18") (pinfunction "PVDDAD33C_18") (pintype "power_in"))
    )
  )
)
